# Bootcamp_Schematic.net
KiCad netlist of a schematic drawn in Altium Designer
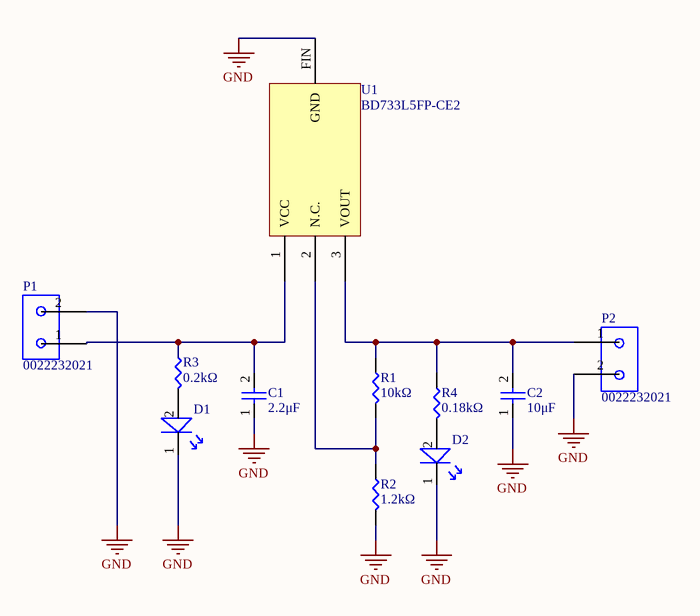
[diagram p0: Bootcamp Schematic.SchDoc]

(export (version "E")
  (design (tool "Eeschema 10.0.6"))
  (components
    (comp (ref "C1")
      (value "2.2μF")
      (footprint "CAP0201 (0603 Metric)")
      (description "CAP CER 2.2UF 4V X5R 0201")
      (fields (field (name "Comment") "GRM033R60G225ME44D"))
      (libsource (lib "Bootcamp_Schematic_Library") (part "GRM033R60G225ME44D"))
    )
    (comp (ref "C2")
      (value "10μF")
      (footprint "CAP0805 (2012 Metric)")
      (description "CAP CER 10UF 6.3V X7R 0805")
      (fields (field (name "Comment") "GRM21BR70J106KA73K"))
      (libsource (lib "Bootcamp_Schematic_Library") (part "GRM21BR70J106KA73K"))
    )
    (comp (ref "D1")
      (value "SML-D12M1WT86")
      (footprint "LED0603Y")
      (description "LED YLW/GREEN DIFFUSED 1608 SMD")
      (libsource (lib "Bootcamp_Schematic_Library") (part "SML-D12M1WT86"))
    )
    (comp (ref "D2")
      (value "SML-D12M1WT86")
      (footprint "LED0603Y")
      (description "LED YLW/GREEN DIFFUSED 1608 SMD")
      (libsource (lib "Bootcamp_Schematic_Library") (part "SML-D12M1WT86"))
    )
    (comp (ref "P1")
      (value "0022232021")
      (footprint "CON2.54mm")
      (description "CONN HEADER VERT 2POS 2.54MM")
      (libsource (lib "") (part "0022232021_1"))
    )
    (comp (ref "P2")
      (value "0022232021")
      (footprint "CON2.54mm")
      (description "CONN HEADER VERT 2POS 2.54MM")
      (libsource (lib "Bootcamp_Schematic_Library") (part "0022232021"))
    )
    (comp (ref "R1")
      (value "10kΩ")
      (footprint "RES0402 (1005 Metric)")
      (description "RES SMD 10K OHM 1% 1/16W 0402")
      (fields (field (name "Comment") "AC0402FR-0710KL"))
      (libsource (lib "Bootcamp_Schematic_Library") (part "AC0402FR-0710KL"))
    )
    (comp (ref "R2")
      (value "1.2kΩ")
      (footprint "RES0402 (1005 Metric)")
      (description "RES 1.2K OHM 5% 1/16W 0402")
      (fields (field (name "Comment") "RC0402JR-071K2L"))
      (libsource (lib "Bootcamp_Schematic_Library") (part "RC0402JR-071K2L"))
    )
    (comp (ref "R3")
      (value "0.2kΩ")
      (footprint "RES0402 (1005 Metric)")
      (description "RES 200 OHM 1% 1/16W 0402")
      (fields (field (name "Comment") "RC0402FR-07200RL"))
      (libsource (lib "Bootcamp_Schematic_Library") (part "RC0402FR-07200RL"))
    )
    (comp (ref "R4")
      (value "0.18kΩ")
      (footprint "RES0402 (1005 Metric)")
      (description "RES 180 OHM 1% 1/16W 0402")
      (fields (field (name "Comment") "RC0402FR-07180RL"))
      (libsource (lib "Bootcamp_Schematic_Library") (part "RC0402FR-07180RL"))
    )
    (comp (ref "U1")
      (value "BD733L5FP-CE2")
      (footprint "TO-252-3, DPak (2 Leads + Tab), SC-63")
      (description "IC REG LINEAR 3.3V 500MA TO252-3")
      (libsource (lib "Bootcamp_Schematic_Library") (part "BD733L5FP-CE2"))
    )
  )
  (nets
    (net (code "1") (name "GND") (class "Default")
      (node (ref "C1") (pin "1") (pinfunction "1_1") (pintype "passive"))
      (node (ref "C2") (pin "1") (pinfunction "1_1") (pintype "passive"))
      (node (ref "D1") (pin "1") (pintype "passive"))
      (node (ref "D2") (pin "1") (pintype "passive"))
      (node (ref "P1") (pin "2") (pintype "passive"))
      (node (ref "P2") (pin "2") (pintype "passive"))
      (node (ref "R2") (pin "1") (pinfunction "1_1") (pintype "passive"))
      (node (ref "U1") (pin "FIN") (pinfunction "GND_FIN") (pintype "passive"))
    )
    (net (code "2") (name "Net-(U1-N.C.)") (class "Default")
      (node (ref "R1") (pin "1") (pinfunction "1_1") (pintype "passive"))
      (node (ref "R2") (pin "2") (pinfunction "2_2") (pintype "passive"))
      (node (ref "U1") (pin "2") (pinfunction "N.C._2") (pintype "passive"))
    )
    (net (code "3") (name "Net-(U1-VCC)") (class "Default")
      (node (ref "C1") (pin "2") (pinfunction "2_2") (pintype "passive"))
      (node (ref "P1") (pin "1") (pintype "passive"))
      (node (ref "R3") (pin "2") (pinfunction "2_2") (pintype "passive"))
      (node (ref "U1") (pin "1") (pinfunction "VCC_1") (pintype "passive"))
    )
    (net (code "4") (name "Net-(U1-VOUT)") (class "Default")
      (node (ref "C2") (pin "2") (pinfunction "2_2") (pintype "passive"))
      (node (ref "P2") (pin "1") (pintype "passive"))
      (node (ref "R1") (pin "2") (pinfunction "2_2") (pintype "passive"))
      (node (ref "R4") (pin "2") (pinfunction "2_2") (pintype "passive"))
      (node (ref "U1") (pin "3") (pinfunction "VOUT_3") (pintype "passive"))
    )
    (net (code "5") (name "unconnected-(D1-Pad2)") (class "Default")
      (node (ref "D1") (pin "2") (pintype "passive"))
    )
    (net (code "6") (name "unconnected-(D2-Pad2)") (class "Default")
      (node (ref "D2") (pin "2") (pintype "passive"))
    )
    (net (code "7") (name "unconnected-(R3-Pad1)") (class "Default")
      (node (ref "R3") (pin "1") (pinfunction "1_1") (pintype "passive"))
    )
    (net (code "8") (name "unconnected-(R4-Pad1)") (class "Default")
      (node (ref "R4") (pin "1") (pinfunction "1_1") (pintype "passive"))
    )
  )
)
